# MacSet-L-V2_0_0_3.net
KiCad netlist of a schematic drawn in Altium Designer
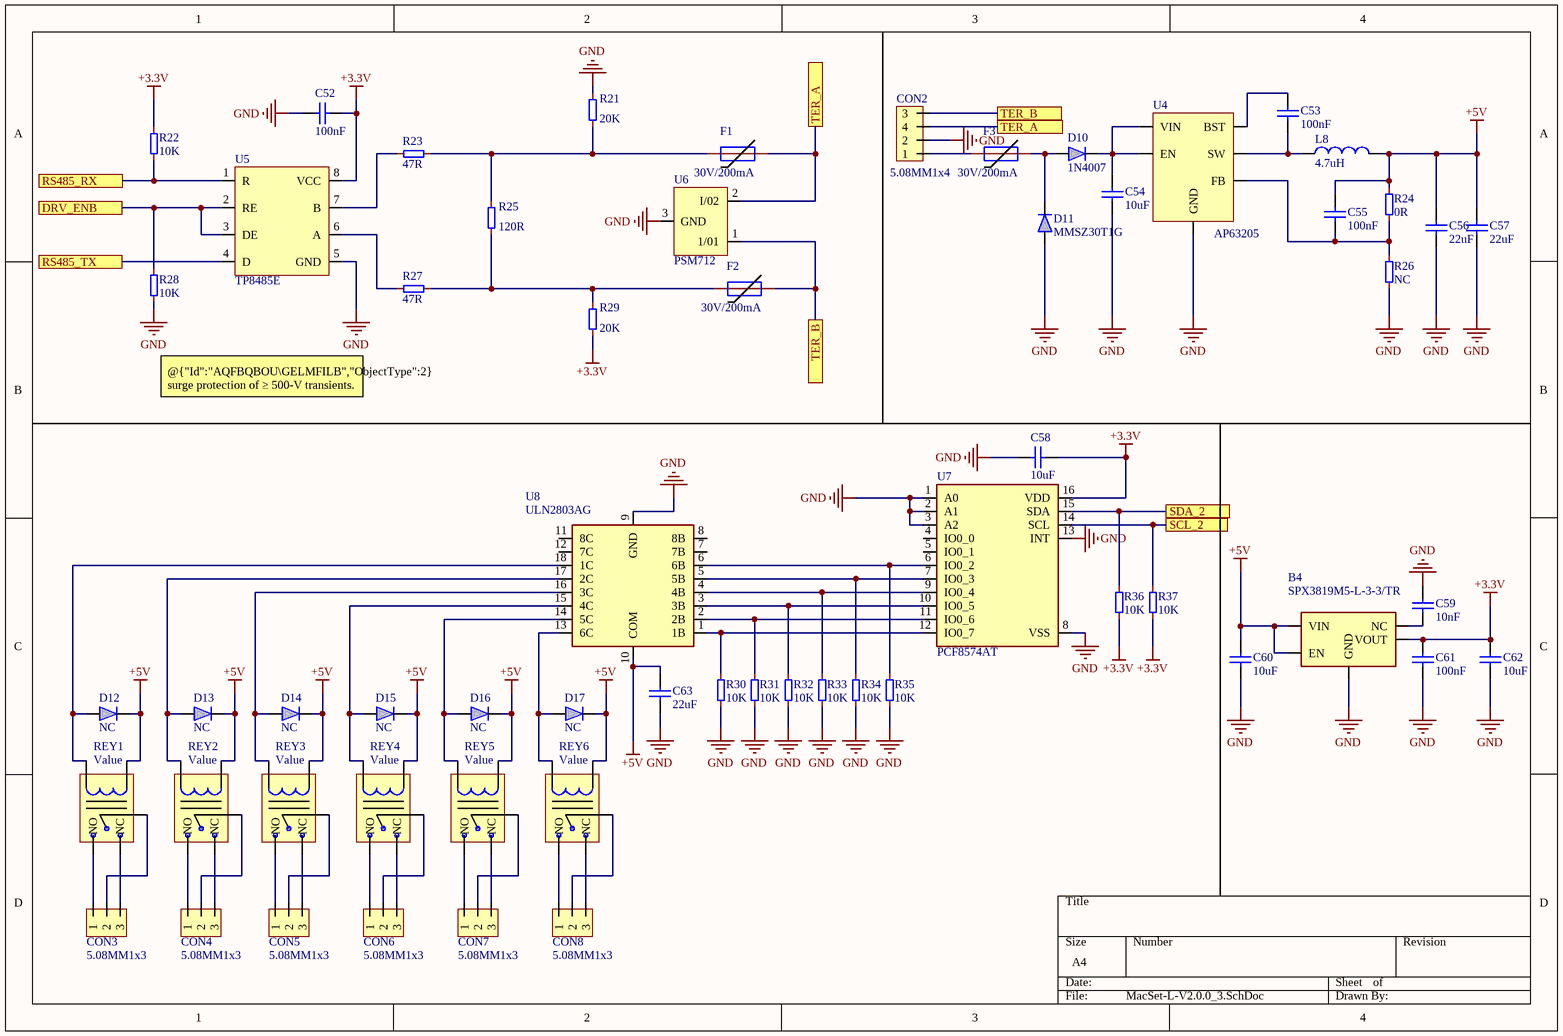
[diagram p0: MacSet-L-V2.0.0_3.SchDoc]

(export (version "E")
  (design (tool "Eeschema 10.0.6"))
  (components
    (comp (ref "B4")
      (value "SPX3819M5-L-3-3/TR")
      (footprint "SOT95P285X140-5N")
      (description "Linear Voltage Regulator IC Positive Fixed 1 3.3V Output 500mA SOT-25")
      (fields (field (name "MANUFACTURER") "MAX Linear"))
      (libsource (lib "macnman_2.0") (part "SPX3819M5"))
    )
    (comp (ref "C52")
      (value "100nF")
      (footprint "CAP0402")
      (description "Ceramic Capacitor X7R 0402 100nF 16V")
      (fields
        (field (name "MANUFACTURER_PART_NUMBER") "GRM155R71C104JA88D")
        (field (name "MANUFACTURER") "MURATA")
      )
      (libsource (lib "macnman_2.0") (part "Capa_0402"))
    )
    (comp (ref "C53")
      (value "100nF")
      (footprint "CAP0402")
      (description "Ceramic Capacitor C0G, NP0 0402 100nF 35V")
      (fields
        (field (name "MANUFACTURER_PART_NUMBER") "GRM155R61A104KA01J")
        (field (name "MANUFACTURER") "MURATA")
      )
      (libsource (lib "macnman_2.0") (part "Capa_0402"))
    )
    (comp (ref "C54")
      (value "10uF")
      (footprint "CAP0805")
      (description "MLCC - SMD/SMT 10 uF 50VDC 10% 0805 X6S")
      (fields
        (field (name "MANUFACTURER_PART_NUMBER") "CC0805KKX5R9BB106")
        (field (name "MANUFACTURER") "YAGEO")
      )
      (libsource (lib "macnman_2.0") (part "Capa_0805"))
    )
    (comp (ref "C55")
      (value "100nF")
      (footprint "CAP0402")
      (description "Ceramic Capacitor C0G, NP0 0402 100nF 35V")
      (fields
        (field (name "MANUFACTURER_PART_NUMBER") "GRM155R61A104KA01J")
        (field (name "MANUFACTURER") "MURATA")
      )
      (libsource (lib "macnman_2.0") (part "Capa_0402"))
    )
    (comp (ref "C56")
      (value "22uF")
      (footprint "CAP0805")
      (description "MLCC - SMD/SMT 22uF 10VDC 20% 0805 X6S")
      (fields
        (field (name "MANUFACTURER_PART_NUMBER") "CC0805KKX7R6BB226")
        (field (name "MANUFACTURER") "YAGEO")
      )
      (libsource (lib "macnman_2.0") (part "Capa_0805"))
    )
    (comp (ref "C57")
      (value "22uF")
      (footprint "CAP0805")
      (description "MLCC - SMD/SMT 22uF 10VDC 20% 0805 X6S")
      (fields
        (field (name "MANUFACTURER_PART_NUMBER") "CC0805KKX7R6BB226")
        (field (name "MANUFACTURER") "MURATA")
      )
      (libsource (lib "macnman_2.0") (part "Capa_0805"))
    )
    (comp (ref "C58")
      (value "10uF")
      (footprint "CAP0603")
      (description "Ceramic Capacitor X5R 0603 10uF 10V")
      (fields
        (field (name "MANUFACTURER_PART_NUMBER") "CL10A106KP8NNNL")
        (field (name "MANUFACTURER") "SAMSUNG")
      )
      (libsource (lib "macnman_2.0") (part "CAP_0603"))
    )
    (comp (ref "C59")
      (value "10nF")
      (footprint "CAP0402")
      (description "Ceramic Capacitor X7R 0402 10nF 50V")
      (fields
        (field (name "MANUFACTURER_PART_NUMBER") "GCM155R71H103KA55J")
        (field (name "MANUFACTURER") "Murata")
      )
      (libsource (lib "macnman_2.0") (part "CAP_0402"))
    )
    (comp (ref "C60")
      (value "10uF")
      (footprint "CAP0603")
      (description "Ceramic Capacitor X5R 0603 10uF 25V")
      (fields
        (field (name "MANUFACTURER_PART_NUMBER") "CL10A106MA8NRNC")
        (field (name "MANUFACTURER") "SAMSUNG")
      )
      (libsource (lib "macnman_2.0") (part "CAP_0603"))
    )
    (comp (ref "C61")
      (value "100nF")
      (footprint "CAP0402")
      (description "Ceramic Capacitor X7R 0402 100nF 50V")
      (fields
        (field (name "MANUFACTURER_PART_NUMBER") "CL05B104KA5NNNC")
        (field (name "MANUFACTURER") "SAMSUNG")
      )
      (libsource (lib "macnman_2.0") (part "CAP_0402"))
    )
    (comp (ref "C62")
      (value "10uF")
      (footprint "CAP0603")
      (description "Ceramic Capacitor X5R 0603 10uF 25V")
      (fields
        (field (name "MANUFACTURER_PART_NUMBER") "CL10A106MA8NRNC")
        (field (name "MANUFACTURER") "SAMSUNG")
      )
      (libsource (lib "macnman_2.0") (part "CAP_0603"))
    )
    (comp (ref "C63")
      (value "22uF")
      (footprint "CAP0805")
      (description "MLCC - SMD/SMT 22uF 10VDC 20% 0805 X6S")
      (fields
        (field (name "MANUFACTURER_PART_NUMBER") "CC0805KKX7R6BB226")
        (field (name "MANUFACTURER") "MURATA")
      )
      (libsource (lib "macnman_2.0") (part "Capa_0805"))
    )
    (comp (ref "CON2")
      (value "5.08MM1x4")
      (footprint "Screw Terminal Block 5.08x4")
      (description "5.08mm 1*4 Screw Terminal Block")
      (fields (field (name "MANUFACTURER") "XINYA"))
      (libsource (lib "macnman_2.0") (part "Screw Terminal Block 4x1 5.08mm"))
    )
    (comp (ref "CON3")
      (value "5.08MM1x3")
      (footprint "Screw Terminal Block 5.08x3")
      (description "5.08mm 1*3 Screw Terminal Block")
      (fields (field (name "MANUFACTURER_PART_NUMBER") "XY302V-3.5-3P") (field (name "MANUFACTURER") "XINYA"))
      (libsource (lib "macnman_2.0") (part "Screw Terminal Block 3x1 5.08mm"))
    )
    (comp (ref "CON4")
      (value "5.08MM1x3")
      (footprint "Screw Terminal Block 5.08x3")
      (description "5.08mm 1*3 Screw Terminal Block")
      (fields (field (name "MANUFACTURER_PART_NUMBER") "XY302V-3.5-3P") (field (name "MANUFACTURER") "XINYA"))
      (libsource (lib "macnman_2.0") (part "Screw Terminal Block 3x1 5.08mm"))
    )
    (comp (ref "CON5")
      (value "5.08MM1x3")
      (footprint "Screw Terminal Block 5.08x3")
      (description "5.08mm 1*3 Screw Terminal Block")
      (fields (field (name "MANUFACTURER_PART_NUMBER") "XY302V-3.5-3P") (field (name "MANUFACTURER") "XINYA"))
      (libsource (lib "macnman_2.0") (part "Screw Terminal Block 3x1 5.08mm"))
    )
    (comp (ref "CON6")
      (value "5.08MM1x3")
      (footprint "Screw Terminal Block 5.08x3")
      (description "5.08mm 1*3 Screw Terminal Block")
      (fields (field (name "MANUFACTURER_PART_NUMBER") "XY302V-3.5-3P") (field (name "MANUFACTURER") "XINYA"))
      (libsource (lib "macnman_2.0") (part "Screw Terminal Block 3x1 5.08mm"))
    )
    (comp (ref "CON7")
      (value "5.08MM1x3")
      (footprint "Screw Terminal Block 5.08x3")
      (description "5.08mm 1*3 Screw Terminal Block")
      (fields (field (name "MANUFACTURER_PART_NUMBER") "XY302V-3.5-3P") (field (name "MANUFACTURER") "XINYA"))
      (libsource (lib "macnman_2.0") (part "Screw Terminal Block 3x1 5.08mm"))
    )
    (comp (ref "CON8")
      (value "5.08MM1x3")
      (footprint "Screw Terminal Block 5.08x3")
      (description "5.08mm 1*3 Screw Terminal Block")
      (fields (field (name "MANUFACTURER_PART_NUMBER") "XY302V-3.5-3P") (field (name "MANUFACTURER") "XINYA"))
      (libsource (lib "macnman_2.0") (part "Screw Terminal Block 3x1 5.08mm"))
    )
    (comp (ref "D10")
      (value "1N4007")
      (footprint "Diode SMD 214AC")
      (description "Diode 1N4007 AO214AC")
      (fields (field (name "MANUFACTURER") "GENERIC"))
      (libsource (lib "macnman_2.0") (part "DIODE"))
    )
    (comp (ref "D11")
      (value "MMSZ30T1G")
      (footprint "SOD123-2")
      (description "MMSZ30T1G 30V 500mW Schottky Diodes & Rectifiers")
      (fields (field (name "MANUFACTURER") "Onsemi"))
      (libsource (lib "macnman_2.0") (part "BAT54T1G"))
    )
    (comp (ref "D12")
      (value "NC")
      (footprint "Diode SMD 214AC")
      (description "Diode 1N4007 AO214AC")
      (fields (field (name "MANUFACTURER_PART_NUMBER") "1N4007") (field (name "MANUFACTURER") "GENERIC"))
      (libsource (lib "macnman_2.0") (part "DIODE"))
    )
    (comp (ref "D13")
      (value "NC")
      (footprint "Diode SMD 214AC")
      (description "Diode 1N4007 AO214AC")
      (fields (field (name "MANUFACTURER_PART_NUMBER") "1N4007") (field (name "MANUFACTURER") "GENERIC"))
      (libsource (lib "macnman_2.0") (part "DIODE"))
    )
    (comp (ref "D14")
      (value "NC")
      (footprint "Diode SMD 214AC")
      (description "Diode 1N4007 AO214AC")
      (fields (field (name "MANUFACTURER_PART_NUMBER") "1N4007") (field (name "MANUFACTURER") "GENERIC"))
      (libsource (lib "macnman_2.0") (part "DIODE"))
    )
    (comp (ref "D15")
      (value "NC")
      (footprint "Diode SMD 214AC")
      (description "Diode 1N4007 AO214AC")
      (fields (field (name "MANUFACTURER_PART_NUMBER") "1N4007") (field (name "MANUFACTURER") "GENERIC"))
      (libsource (lib "macnman_2.0") (part "DIODE"))
    )
    (comp (ref "D16")
      (value "NC")
      (footprint "Diode SMD 214AC")
      (description "Diode 1N4007 AO214AC")
      (fields (field (name "MANUFACTURER_PART_NUMBER") "1N4007") (field (name "MANUFACTURER") "GENERIC"))
      (libsource (lib "macnman_2.0") (part "DIODE"))
    )
    (comp (ref "D17")
      (value "NC")
      (footprint "Diode SMD 214AC")
      (description "Diode 1N4007 AO214AC")
      (fields (field (name "MANUFACTURER_PART_NUMBER") "1N4007") (field (name "MANUFACTURER") "GENERIC"))
      (libsource (lib "macnman_2.0") (part "DIODE"))
    )
    (comp (ref "F1")
      (value "30V/200mA")
      (footprint "FUSE_1206")
      (description "Polymeric PTC Resettable Fuse 30V 200mA Surface Mount 1206")
      (fields
        (field (name "MANUFACTURER_PART_NUMBER") "nSMD020-30V")
        (field (name "MANUFACTURER") "TECHFUSE")
      )
      (libsource (lib "macnman_2.0") (part "FUSE_1206"))
    )
    (comp (ref "F2")
      (value "30V/200mA")
      (footprint "FUSE_1206")
      (description "Polymeric PTC Resettable Fuse 30V 200mA Surface Mount 1206")
      (fields
        (field (name "MANUFACTURER_PART_NUMBER") "nSMD020-30V")
        (field (name "MANUFACTURER") "TECHFUSE")
      )
      (libsource (lib "macnman_2.0") (part "FUSE_1206"))
    )
    (comp (ref "F3")
      (value "30V/200mA")
      (footprint "FUSE_1206")
      (description "Polymeric PTC Resettable Fuse 30V 200mA Surface Mount 1206")
      (fields
        (field (name "MANUFACTURER_PART_NUMBER") "nSMD020-30V")
        (field (name "MANUFACTURER") "TECHFUSE")
      )
      (libsource (lib "macnman_2.0") (part "FUSE_1206"))
    )
    (comp (ref "L8")
      (value "4.7uH")
      (footprint "IND_3x3x1.5MM")
      (description "1.09A 4.7uH ±3% 163mΩ 3015 Inductors")
      (fields
        (field (name "MANUFACTURER_PART_NUMBER") "SWPA3015S4R7MT")
        (field (name "MANUFACTURER") "SUNLORD")
      )
      (libsource (lib "macnman_2.0") (part "INDUCTOR"))
    )
    (comp (ref "R21")
      (value "20K")
      (footprint "RESC0402")
      (description "Resistor SMD 0402")
      (fields
        (field (name "MANUFACTURER_PART_NUMBER") "CRCW040220K0FKEDC")
        (field (name "MANUFACTURER") "YAGEO")
      )
      (libsource (lib "macnman_2.0") (part "RES_0402"))
    )
    (comp (ref "R22")
      (value "10K")
      (footprint "RESC0402")
      (description "Thick Film Resistors - SMD 1/16watt 10Kohms 0402 1% Commercial Use")
      (fields
        (field (name "MANUFACTURER_PART_NUMBER") "CRCW040210K0FKEDC")
        (field (name "MANUFACTURER") "Vishay")
      )
      (libsource (lib "macnman_2.0") (part "RES_0402"))
    )
    (comp (ref "R23")
      (value "47R")
      (footprint "RESC0603")
      (description "Thick Film Resistors - SMD 1/16Watt 47ohms 1% Commercial Use")
      (fields
        (field (name "MANUFACTURER_PART_NUMBER") "RC0402FR-0747RL")
        (field (name "MANUFACTURER") "Vishay")
      )
      (libsource (lib "macnman_2.0") (part "RES_0603"))
    )
    (comp (ref "R24")
      (value "0R")
      (footprint "RESC0402")
      (description "Thick Film Resistors - SMD 1/16watt 0R 1% 0402 Commercial Use")
      (fields
        (field (name "MANUFACTURER_PART_NUMBER") "RC0402FR-070RL")
        (field (name "MANUFACTURER") "Vishay")
      )
      (libsource (lib "macnman_2.0") (part "RES_0402"))
    )
    (comp (ref "R25")
      (value "120R")
      (footprint "RESC0402")
      (description "Resistor SMD 0402")
      (fields (field (name "Comment") "NC"))
      (libsource (lib "macnman_2.0") (part "RES_0402"))
    )
    (comp (ref "R26")
      (value "NC")
      (footprint "RESC0402")
      (description "Thick Film Resistors - SMD 1/16watt 10Kohms 0.1% 0402 Commercial Use")
      (fields
        (field (name "MANUFACTURER_PART_NUMBER") "MCS04020D1002BE000")
        (field (name "MANUFACTURER") "Vishay")
      )
      (libsource (lib "macnman_2.0") (part "RES_0402"))
    )
    (comp (ref "R27")
      (value "47R")
      (footprint "RESC0603")
      (description "Thick Film Resistors - SMD 1/16Watt 47ohms 1% Commercial Use")
      (fields
        (field (name "MANUFACTURER_PART_NUMBER") "RC0402FR-0747RL")
        (field (name "MANUFACTURER") "Vishay")
      )
      (libsource (lib "macnman_2.0") (part "RES_0603"))
    )
    (comp (ref "R28")
      (value "10K")
      (footprint "RESC0402")
      (description "Thick Film Resistors - SMD 1/16watt 10Kohms 0402 1% Commercial Use")
      (fields
        (field (name "MANUFACTURER_PART_NUMBER") "CRCW040210K0FKEDC")
        (field (name "MANUFACTURER") "Vishay")
      )
      (libsource (lib "macnman_2.0") (part "RES_0402"))
    )
    (comp (ref "R29")
      (value "20K")
      (footprint "RESC0402")
      (description "Resistor SMD 0402")
      (fields
        (field (name "MANUFACTURER_PART_NUMBER") "CRCW040220K0FKEDC")
        (field (name "MANUFACTURER") "YAGEO")
      )
      (libsource (lib "macnman_2.0") (part "RES_0402"))
    )
    (comp (ref "R30")
      (value "10K")
      (footprint "RESC0402")
      (description "Thick Film Resistors - SMD 1/16watt 10Kohms 0402 1% Commercial Use")
      (fields
        (field (name "MANUFACTURER_PART_NUMBER") "CRCW040210K0FKEDC")
        (field (name "MANUFACTURER") "Vishay")
      )
      (libsource (lib "macnman_2.0") (part "RES_0402"))
    )
    (comp (ref "R31")
      (value "10K")
      (footprint "RESC0402")
      (description "Thick Film Resistors - SMD 1/16watt 10Kohms 0402 1% Commercial Use")
      (fields
        (field (name "MANUFACTURER_PART_NUMBER") "CRCW040210K0FKEDC")
        (field (name "MANUFACTURER") "Vishay")
      )
      (libsource (lib "macnman_2.0") (part "RES_0402"))
    )
    (comp (ref "R32")
      (value "10K")
      (footprint "RESC0402")
      (description "Thick Film Resistors - SMD 1/16watt 10Kohms 0402 1% Commercial Use")
      (fields
        (field (name "MANUFACTURER_PART_NUMBER") "CRCW040210K0FKEDC")
        (field (name "MANUFACTURER") "Vishay")
      )
      (libsource (lib "macnman_2.0") (part "RES_0402"))
    )
    (comp (ref "R33")
      (value "10K")
      (footprint "RESC0402")
      (description "Thick Film Resistors - SMD 1/16watt 10Kohms 0402 1% Commercial Use")
      (fields
        (field (name "MANUFACTURER_PART_NUMBER") "CRCW040210K0FKEDC")
        (field (name "MANUFACTURER") "Vishay")
      )
      (libsource (lib "macnman_2.0") (part "RES_0402"))
    )
    (comp (ref "R34")
      (value "10K")
      (footprint "RESC0402")
      (description "Thick Film Resistors - SMD 1/16watt 10Kohms 0402 1% Commercial Use")
      (fields
        (field (name "MANUFACTURER_PART_NUMBER") "CRCW040210K0FKEDC")
        (field (name "MANUFACTURER") "Vishay")
      )
      (libsource (lib "macnman_2.0") (part "RES_0402"))
    )
    (comp (ref "R35")
      (value "10K")
      (footprint "RESC0402")
      (description "Thick Film Resistors - SMD 1/16watt 10Kohms 0402 1% Commercial Use")
      (fields
        (field (name "MANUFACTURER_PART_NUMBER") "CRCW040210K0FKEDC")
        (field (name "MANUFACTURER") "Vishay")
      )
      (libsource (lib "macnman_2.0") (part "RES_0402"))
    )
    (comp (ref "R36")
      (value "10K")
      (footprint "RESC0402")
      (description "Thick Film Resistors - SMD 1/16watt 10Kohms 0402 1% Commercial Use")
      (fields
        (field (name "MANUFACTURER_PART_NUMBER") "CRCW040210K0FKEDC")
        (field (name "MANUFACTURER") "Vishay")
      )
      (libsource (lib "macnman_2.0") (part "RES_0402"))
    )
    (comp (ref "R37")
      (value "10K")
      (footprint "RESC0402")
      (description "Thick Film Resistors - SMD 1/16watt 10Kohms 0402 1% Commercial Use")
      (fields
        (field (name "MANUFACTURER_PART_NUMBER") "CRCW040210K0FKEDC")
        (field (name "MANUFACTURER") "Vishay")
      )
      (libsource (lib "macnman_2.0") (part "RES_0402"))
    )
    (comp (ref "REY1")
      (value "Value")
      (footprint "Relay")
      (description "5V Sugar Cube Relay 44mA")
      (libsource (lib "macnman_2.0") (part "Relay"))
    )
    (comp (ref "REY2")
      (value "Value")
      (footprint "Relay")
      (description "5V Sugar Cube Relay 44mA")
      (libsource (lib "macnman_2.0") (part "Relay"))
    )
    (comp (ref "REY3")
      (value "Value")
      (footprint "Relay")
      (description "5V Sugar Cube Relay 44mA")
      (libsource (lib "macnman_2.0") (part "Relay"))
    )
    (comp (ref "REY4")
      (value "Value")
      (footprint "Relay")
      (description "5V Sugar Cube Relay 44mA")
      (libsource (lib "macnman_2.0") (part "Relay"))
    )
    (comp (ref "REY5")
      (value "Value")
      (footprint "Relay")
      (description "5V Sugar Cube Relay 44mA")
      (libsource (lib "macnman_2.0") (part "Relay"))
    )
    (comp (ref "REY6")
      (value "Value")
      (footprint "Relay")
      (description "5V Sugar Cube Relay 44mA")
      (libsource (lib "macnman_2.0") (part "Relay"))
    )
    (comp (ref "U4")
      (value "AP63205")
      (footprint "SOT23-6")
      (description "AP63205 - Switching Voltage Regulators 5V OUT DCDC 3.8V-32V Conv HV Buck TSOT26 T&R 3K")
      (fields
        (field (name "MANUFACTURER_PART_NUMBER") "AP63205QWU-7")
        (field (name "MANUFACTURER") "Diodes Incorporated")
      )
      (libsource (lib "macnman_2.0") (part "AP63205"))
    )
    (comp (ref "U5")
      (value "TP8485E")
      (footprint "SOIC8")
      (description "TP8485E RS485 Tranreciver 3V-5.5V SOIC8")
      (fields (field (name "MANUFACTURER") "3PEAK") (field (name "MANUFACTURER_PART_NUMBER") "TP8485"))
      (libsource (lib "macnman_2.0") (part "TP8485E"))
    )
    (comp (ref "U6")
      (value "PSM712")
      (footprint "SOT23")
      (description "Asymmerical TVS Diode for Extended Common-Mode RS-485")
      (fields
        (field (name "MANUFACTURER_PART_NUMBER") "SM712H-TP-B002")
        (field (name "MANUFACTURER") "Micro Commercial Components (MCC)")
      )
      (libsource (lib "macnman_2.0") (part "PSM712"))
    )
    (comp (ref "U7")
      (value "PCF8574AT")
      (footprint "SOIC-16-W")
      (description "PCF8574AT 8Bit I2C GPIO Expander 16 Pin")
      (fields (field (name "MANUFACTURER") "NXP Semiconductors"))
      (libsource (lib "macnman_2.0") (part "PCF8574AT"))
    )
    (comp (ref "U8")
      (value "ULN2803AG")
      (footprint "SOIC-18-W")
      (description "ULN2803C device is a 50V, 500mA Darlington\r\ntransistor array")
      (fields (field (name "MANUFACTURER_PART_NUMBER") "ULN2803A") (field (name "MANUFACTURER") "UMW"))
      (libsource (lib "macnman_2.0") (part "ULN2803AG"))
    )
  )
  (nets
    (net (code "1") (name "+3.3V") (class "Default")
      (node (ref "B4") (pin "5") (pinfunction "VOUT_5") (pintype "passive"))
      (node (ref "C52") (pin "2") (pinfunction "2_2") (pintype "passive"))
      (node (ref "C58") (pin "2") (pinfunction "2_2") (pintype "passive"))
      (node (ref "C61") (pin "2") (pinfunction "2_2") (pintype "passive"))
      (node (ref "C62") (pin "2") (pinfunction "2_2") (pintype "passive"))
      (node (ref "R22") (pin "2") (pinfunction "2_2") (pintype "passive"))
      (node (ref "R29") (pin "1") (pinfunction "1_1") (pintype "passive"))
      (node (ref "R36") (pin "1") (pinfunction "1_1") (pintype "passive"))
      (node (ref "R37") (pin "1") (pinfunction "1_1") (pintype "passive"))
      (node (ref "U5") (pin "8") (pinfunction "VCC_8") (pintype "passive"))
      (node (ref "U7") (pin "16") (pinfunction "VDD_16") (pintype "passive"))
    )
    (net (code "2") (name "+5V") (class "Default")
      (node (ref "B4") (pin "1") (pinfunction "VIN_1") (pintype "passive"))
      (node (ref "B4") (pin "3") (pinfunction "EN_3") (pintype "passive"))
      (node (ref "C55") (pin "2") (pinfunction "2_2") (pintype "passive"))
      (node (ref "C56") (pin "2") (pinfunction "2_2") (pintype "passive"))
      (node (ref "C57") (pin "2") (pinfunction "2_2") (pintype "passive"))
      (node (ref "C60") (pin "2") (pinfunction "2_2") (pintype "passive"))
      (node (ref "C63") (pin "1") (pinfunction "1_1") (pintype "passive"))
      (node (ref "D12") (pin "1") (pinfunction "K_1") (pintype "passive"))
      (node (ref "D13") (pin "1") (pinfunction "K_1") (pintype "passive"))
      (node (ref "D14") (pin "1") (pinfunction "K_1") (pintype "passive"))
      (node (ref "D15") (pin "1") (pinfunction "K_1") (pintype "passive"))
      (node (ref "D16") (pin "1") (pinfunction "K_1") (pintype "passive"))
      (node (ref "D17") (pin "1") (pinfunction "K_1") (pintype "passive"))
      (node (ref "L8") (pin "2") (pintype "passive"))
      (node (ref "R24") (pin "1") (pinfunction "1_1") (pintype "passive"))
      (node (ref "REY1") (pin "1") (pinfunction "+_1") (pintype "passive"))
      (node (ref "REY2") (pin "1") (pinfunction "+_1") (pintype "passive"))
      (node (ref "REY3") (pin "1") (pinfunction "+_1") (pintype "passive"))
      (node (ref "REY4") (pin "1") (pinfunction "+_1") (pintype "passive"))
      (node (ref "REY5") (pin "1") (pinfunction "+_1") (pintype "passive"))
      (node (ref "REY6") (pin "1") (pinfunction "+_1") (pintype "passive"))
      (node (ref "U8") (pin "10") (pinfunction "COM_10") (pintype "passive"))
    )
    (net (code "3") (name "/DRV_ENB") (class "Default")
      (node (ref "R28") (pin "2") (pinfunction "2_2") (pintype "passive"))
      (node (ref "U5") (pin "2") (pinfunction "RE_2") (pintype "passive"))
      (node (ref "U5") (pin "3") (pinfunction "DE_3") (pintype "passive"))
    )
    (net (code "4") (name "/RS485_RX") (class "Default")
      (node (ref "R22") (pin "1") (pinfunction "1_1") (pintype "passive"))
      (node (ref "U5") (pin "1") (pinfunction "R_1") (pintype "passive"))
    )
    (net (code "5") (name "/RS485_TX") (class "Default")
      (node (ref "U5") (pin "4") (pinfunction "D_4") (pintype "passive"))
    )
    (net (code "6") (name "/SCL_2") (class "Default")
      (node (ref "R37") (pin "2") (pinfunction "2_2") (pintype "passive"))
      (node (ref "U7") (pin "14") (pinfunction "SCL_14") (pintype "passive"))
    )
    (net (code "7") (name "/SDA_2") (class "Default")
      (node (ref "R36") (pin "2") (pinfunction "2_2") (pintype "passive"))
      (node (ref "U7") (pin "15") (pinfunction "SDA_15") (pintype "passive"))
    )
    (net (code "8") (name "/TER_A") (class "Default")
      (node (ref "CON2") (pin "4") (pinfunction "4_4") (pintype "passive"))
      (node (ref "F1") (pin "2") (pinfunction "50_2") (pintype "passive"))
      (node (ref "U6") (pin "2") (pinfunction "I/02_2") (pintype "passive"))
    )
    (net (code "9") (name "/TER_B") (class "Default")
      (node (ref "CON2") (pin "3") (pinfunction "3_3") (pintype "passive"))
      (node (ref "F2") (pin "2") (pinfunction "50_2") (pintype "passive"))
      (node (ref "U6") (pin "1") (pinfunction "1/01_1") (pintype "passive"))
    )
    (net (code "10") (name "GND") (class "Default")
      (node (ref "B4") (pin "2") (pinfunction "GND_2") (pintype "passive"))
      (node (ref "C52") (pin "1") (pinfunction "1_1") (pintype "passive"))
      (node (ref "C54") (pin "1") (pinfunction "1_1") (pintype "passive"))
      (node (ref "C56") (pin "1") (pinfunction "1_1") (pintype "passive"))
      (node (ref "C57") (pin "1") (pinfunction "1_1") (pintype "passive"))
      (node (ref "C58") (pin "1") (pinfunction "1_1") (pintype "passive"))
      (node (ref "C59") (pin "1") (pinfunction "1_1") (pintype "passive"))
      (node (ref "C60") (pin "1") (pinfunction "1_1") (pintype "passive"))
      (node (ref "C61") (pin "1") (pinfunction "1_1") (pintype "passive"))
      (node (ref "C62") (pin "1") (pinfunction "1_1") (pintype "passive"))
      (node (ref "C63") (pin "2") (pinfunction "2_2") (pintype "passive"))
      (node (ref "CON2") (pin "2") (pinfunction "2_2") (pintype "passive"))
      (node (ref "D11") (pin "2") (pinfunction "A_2") (pintype "passive"))
      (node (ref "R21") (pin "2") (pinfunction "2_2") (pintype "passive"))
      (node (ref "R26") (pin "2") (pinfunction "2_2") (pintype "passive"))
      (node (ref "R28") (pin "1") (pinfunction "1_1") (pintype "passive"))
      (node (ref "R30") (pin "1") (pinfunction "1_1") (pintype "passive"))
      (node (ref "R31") (pin "1") (pinfunction "1_1") (pintype "passive"))
      (node (ref "R32") (pin "1") (pinfunction "1_1") (pintype "passive"))
      (node (ref "R33") (pin "1") (pinfunction "1_1") (pintype "passive"))
      (node (ref "R34") (pin "1") (pinfunction "1_1") (pintype "passive"))
      (node (ref "R35") (pin "1") (pinfunction "1_1") (pintype "passive"))
      (node (ref "U4") (pin "4") (pinfunction "GND_4") (pintype "passive"))
      (node (ref "U5") (pin "5") (pinfunction "GND_5") (pintype "passive"))
      (node (ref "U6") (pin "3") (pinfunction "GND_3") (pintype "passive"))
      (node (ref "U7") (pin "1") (pinfunction "A0_1") (pintype "power_in"))
      (node (ref "U7") (pin "13") (pinfunction "INT_13") (pintype "passive"))
      (node (ref "U7") (pin "2") (pinfunction "A1_2") (pintype "power_in"))
      (node (ref "U7") (pin "3") (pinfunction "A2_3") (pintype "passive"))
      (node (ref "U7") (pin "8") (pinfunction "VSS_8") (pintype "passive"))
      (node (ref "U8") (pin "9") (pinfunction "GND_9") (pintype "passive"))
    )
    (net (code "11") (name "Net-(B4-NC)") (class "Default")
      (node (ref "B4") (pin "4") (pinfunction "NC_4") (pintype "passive"))
      (node (ref "C59") (pin "2") (pinfunction "2_2") (pintype "passive"))
    )
    (net (code "12") (name "Net-(D10-A)") (class "Default")
      (node (ref "D10") (pin "2") (pinfunction "A_2") (pintype "passive"))
      (node (ref "D11") (pin "1") (pinfunction "K_1") (pintype "passive"))
      (node (ref "F3") (pin "2") (pinfunction "50_2") (pintype "passive"))
    )
    (net (code "13") (name "Net-(D10-K)") (class "Default")
      (node (ref "C54") (pin "2") (pinfunction "2_2") (pintype "passive"))
      (node (ref "D10") (pin "1") (pinfunction "K_1") (pintype "passive"))
      (node (ref "U4") (pin "2") (pinfunction "EN_2") (pintype "passive"))
      (node (ref "U4") (pin "3") (pinfunction "VIN_3") (pintype "passive"))
    )
    (net (code "14") (name "Net-(D12-A)") (class "Default")
      (node (ref "D12") (pin "2") (pinfunction "A_2") (pintype "passive"))
      (node (ref "REY1") (pin "3") (pinfunction "-_3") (pintype "passive"))
      (node (ref "U8") (pin "18") (pinfunction "1C_18") (pintype "passive"))
    )
    (net (code "15") (name "Net-(D13-A)") (class "Default")
      (node (ref "D13") (pin "2") (pinfunction "A_2") (pintype "passive"))
      (node (ref "REY2") (pin "3") (pinfunction "-_3") (pintype "passive"))
      (node (ref "U8") (pin "17") (pinfunction "2C_17") (pintype "passive"))
    )
    (net (code "16") (name "Net-(D14-A)") (class "Default")
      (node (ref "D14") (pin "2") (pinfunction "A_2") (pintype "passive"))
      (node (ref "REY3") (pin "3") (pinfunction "-_3") (pintype "passive"))
      (node (ref "U8") (pin "16") (pinfunction "3C_16") (pintype "passive"))
    )
    (net (code "17") (name "Net-(D15-A)") (class "Default")
      (node (ref "D15") (pin "2") (pinfunction "A_2") (pintype "passive"))
      (node (ref "REY4") (pin "3") (pinfunction "-_3") (pintype "passive"))
      (node (ref "U8") (pin "15") (pinfunction "4C_15") (pintype "passive"))
    )
    (net (code "18") (name "Net-(D16-A)") (class "Default")
      (node (ref "D16") (pin "2") (pinfunction "A_2") (pintype "passive"))
      (node (ref "REY5") (pin "3") (pinfunction "-_3") (pintype "passive"))
      (node (ref "U8") (pin "14") (pinfunction "5C_14") (pintype "passive"))
    )
    (net (code "19") (name "Net-(D17-A)") (class "Default")
      (node (ref "D17") (pin "2") (pinfunction "A_2") (pintype "passive"))
      (node (ref "REY6") (pin "3") (pinfunction "-_3") (pintype "passive"))
      (node (ref "U8") (pin "13") (pinfunction "6C_13") (pintype "passive"))
    )
    (net (code "20") (name "Net-(F1-49)") (class "Default")
      (node (ref "F1") (pin "1") (pinfunction "49_1") (pintype "passive"))
      (node (ref "R21") (pin "1") (pinfunction "1_1") (pintype "passive"))
      (node (ref "R23") (pin "2") (pinfunction "2_2") (pintype "passive"))
      (node (ref "R25") (pin "2") (pinfunction "2_2") (pintype "passive"))
    )
    (net (code "21") (name "Net-(F2-49)") (class "Default")
      (node (ref "F2") (pin "1") (pinfunction "49_1") (pintype "passive"))
      (node (ref "R25") (pin "1") (pinfunction "1_1") (pintype "passive"))
      (node (ref "R27") (pin "2") (pinfunction "2_2") (pintype "passive"))
      (node (ref "R29") (pin "2") (pinfunction "2_2") (pintype "passive"))
    )
    (net (code "22") (name "Net-(F3-49)") (class "Default")
      (node (ref "CON2") (pin "1") (pinfunction "1_1") (pintype "passive"))
      (node (ref "F3") (pin "1") (pinfunction "49_1") (pintype "passive"))
    )
    (net (code "23") (name "Net-(REY1-CM)") (class "Default")
      (node (ref "CON3") (pin "2") (pinfunction "2_2") (pintype "passive"))
      (node (ref "REY1") (pin "2") (pinfunction "CM_2") (pintype "passive"))
    )
    (net (code "24") (name "Net-(REY1-NC)") (class "Default")
      (node (ref "CON3") (pin "3") (pinfunction "3_3") (pintype "passive"))
      (node (ref "REY1") (pin "5") (pinfunction "NC_5") (pintype "passive"))
    )
    (net (code "25") (name "Net-(REY1-NO)") (class "Default")
      (node (ref "CON3") (pin "1") (pinfunction "1_1") (pintype "passive"))
      (node (ref "REY1") (pin "4") (pinfunction "NO_4") (pintype "passive"))
    )
    (net (code "26") (name "Net-(REY2-CM)") (class "Default")
      (node (ref "CON4") (pin "2") (pinfunction "2_2") (pintype "passive"))
      (node (ref "REY2") (pin "2") (pinfunction "CM_2") (pintype "passive"))
    )
    (net (code "27") (name "Net-(REY2-NC)") (class "Default")
      (node (ref "CON4") (pin "3") (pinfunction "3_3") (pintype "passive"))
      (node (ref "REY2") (pin "5") (pinfunction "NC_5") (pintype "passive"))
    )
    (net (code "28") (name "Net-(REY2-NO)") (class "Default")
      (node (ref "CON4") (pin "1") (pinfunction "1_1") (pintype "passive"))
      (node (ref "REY2") (pin "4") (pinfunction "NO_4") (pintype "passive"))
    )
    (net (code "29") (name "Net-(REY3-CM)") (class "Default")
      (node (ref "CON5") (pin "2") (pinfunction "2_2") (pintype "passive"))
      (node (ref "REY3") (pin "2") (pinfunction "CM_2") (pintype "passive"))
    )
    (net (code "30") (name "Net-(REY3-NC)") (class "Default")
      (node (ref "CON5") (pin "3") (pinfunction "3_3") (pintype "passive"))
      (node (ref "REY3") (pin "5") (pinfunction "NC_5") (pintype "passive"))
    )
    (net (code "31") (name "Net-(REY3-NO)") (class "Default")
      (node (ref "CON5") (pin "1") (pinfunction "1_1") (pintype "passive"))
      (node (ref "REY3") (pin "4") (pinfunction "NO_4") (pintype "passive"))
    )
    (net (code "32") (name "Net-(REY4-CM)") (class "Default")
      (node (ref "CON6") (pin "2") (pinfunction "2_2") (pintype "passive"))
      (node (ref "REY4") (pin "2") (pinfunction "CM_2") (pintype "passive"))
    )
    (net (code "33") (name "Net-(REY4-NC)") (class "Default")
      (node (ref "CON6") (pin "3") (pinfunction "3_3") (pintype "passive"))
      (node (ref "REY4") (pin "5") (pinfunction "NC_5") (pintype "passive"))
    )
    (net (code "34") (name "Net-(REY4-NO)") (class "Default")
      (node (ref "CON6") (pin "1") (pinfunction "1_1") (pintype "passive"))
      (node (ref "REY4") (pin "4") (pinfunction "NO_4") (pintype "passive"))
    )
    (net (code "35") (name "Net-(REY5-CM)") (class "Default")
      (node (ref "CON7") (pin "2") (pinfunction "2_2") (pintype "passive"))
      (node (ref "REY5") (pin "2") (pinfunction "CM_2") (pintype "passive"))
    )
    (net (code "36") (name "Net-(REY5-NC)") (class "Default")
      (node (ref "CON7") (pin "3") (pinfunction "3_3") (pintype "passive"))
      (node (ref "REY5") (pin "5") (pinfunction "NC_5") (pintype "passive"))
    )
    (net (code "37") (name "Net-(REY5-NO)") (class "Default")
      (node (ref "CON7") (pin "1") (pinfunction "1_1") (pintype "passive"))
      (node (ref "REY5") (pin "4") (pinfunction "NO_4") (pintype "passive"))
    )
    (net (code "38") (name "Net-(REY6-CM)") (class "Default")
      (node (ref "CON8") (pin "2") (pinfunction "2_2") (pintype "passive"))
      (node (ref "REY6") (pin "2") (pinfunction "CM_2") (pintype "passive"))
    )
    (net (code "39") (name "Net-(REY6-NC)") (class "Default")
      (node (ref "CON8") (pin "3") (pinfunction "3_3") (pintype "passive"))
      (node (ref "REY6") (pin "5") (pinfunction "NC_5") (pintype "passive"))
    )
    (net (code "40") (name "Net-(REY6-NO)") (class "Default")
      (node (ref "CON8") (pin "1") (pinfunction "1_1") (pintype "passive"))
      (node (ref "REY6") (pin "4") (pinfunction "NO_4") (pintype "passive"))
    )
    (net (code "41") (name "Net-(U4-BST)") (class "Default")
      (node (ref "C53") (pin "2") (pinfunction "2_2") (pintype "passive"))
      (node (ref "U4") (pin "6") (pinfunction "BST_6") (pintype "passive"))
    )
    (net (code "42") (name "Net-(U4-FB)") (class "Default")
      (node (ref "C55") (pin "1") (pinfunction "1_1") (pintype "passive"))
      (node (ref "R24") (pin "2") (pinfunction "2_2") (pintype "passive"))
      (node (ref "R26") (pin "1") (pinfunction "1_1") (pintype "passive"))
      (node (ref "U4") (pin "1") (pinfunction "FB_1") (pintype "passive"))
    )
    (net (code "43") (name "Net-(U4-SW)") (class "Default")
      (node (ref "C53") (pin "1") (pinfunction "1_1") (pintype "passive"))
      (node (ref "L8") (pin "1") (pintype "passive"))
      (node (ref "U4") (pin "5") (pinfunction "SW_5") (pintype "passive"))
    )
    (net (code "44") (name "Net-(U5-A)") (class "Default")
      (node (ref "R27") (pin "1") (pinfunction "1_1") (pintype "passive"))
      (node (ref "U5") (pin "6") (pinfunction "A_6") (pintype "passive"))
    )
    (net (code "45") (name "Net-(U5-B)") (class "Default")
      (node (ref "R23") (pin "1") (pinfunction "1_1") (pintype "passive"))
      (node (ref "U5") (pin "7") (pinfunction "B_7") (pintype "passive"))
    )
    (net (code "46") (name "Net-(U7-IO0_2)") (class "Default")
      (node (ref "R35") (pin "2") (pinfunction "2_2") (pintype "passive"))
      (node (ref "U7") (pin "6") (pinfunction "IO0_2_6") (pintype "passive"))
      (node (ref "U8") (pin "6") (pinfunction "6B_6") (pintype "passive"))
    )
    (net (code "47") (name "Net-(U7-IO0_3)") (class "Default")
      (node (ref "R34") (pin "2") (pinfunction "2_2") (pintype "passive"))
      (node (ref "U7") (pin "7") (pinfunction "IO0_3_7") (pintype "passive"))
      (node (ref "U8") (pin "5") (pinfunction "5B_5") (pintype "passive"))
    )
    (net (code "48") (name "Net-(U7-IO0_4)") (class "Default")
      (node (ref "R33") (pin "2") (pinfunction "2_2") (pintype "passive"))
      (node (ref "U7") (pin "9") (pinfunction "IO0_4_9") (pintype "passive"))
      (node (ref "U8") (pin "4") (pinfunction "4B_4") (pintype "passive"))
    )
    (net (code "49") (name "Net-(U7-IO0_5)") (class "Default")
      (node (ref "R32") (pin "2") (pinfunction "2_2") (pintype "passive"))
      (node (ref "U7") (pin "10") (pinfunction "IO0_5_10") (pintype "passive"))
      (node (ref "U8") (pin "3") (pinfunction "3B_3") (pintype "passive"))
    )
    (net (code "50") (name "Net-(U7-IO0_6)") (class "Default")
      (node (ref "R31") (pin "2") (pinfunction "2_2") (pintype "passive"))
      (node (ref "U7") (pin "11") (pinfunction "IO0_6_11") (pintype "passive"))
      (node (ref "U8") (pin "2") (pinfunction "2B_2") (pintype "power_in"))
    )
    (net (code "51") (name "Net-(U7-IO0_7)") (class "Default")
      (node (ref "R30") (pin "2") (pinfunction "2_2") (pintype "passive"))
      (node (ref "U7") (pin "12") (pinfunction "IO0_7_12") (pintype "passive"))
      (node (ref "U8") (pin "1") (pinfunction "1B_1") (pintype "power_in"))
    )
    (net (code "52") (name "unconnected-(U7-IO0_0-Pad4)") (class "Default")
      (node (ref "U7") (pin "4") (pinfunction "IO0_0_4") (pintype "passive"))
    )
    (net (code "53") (name "unconnected-(U7-IO0_1-Pad5)") (class "Default")
      (node (ref "U7") (pin "5") (pinfunction "IO0_1_5") (pintype "passive"))
    )
    (net (code "54") (name "unconnected-(U8-7B-Pad7)") (class "Default")
      (node (ref "U8") (pin "7") (pinfunction "7B_7") (pintype "passive"))
    )
    (net (code "55") (name "unconnected-(U8-7C-Pad12)") (class "Default")
      (node (ref "U8") (pin "12") (pinfunction "7C_12") (pintype "passive"))
    )
    (net (code "56") (name "unconnected-(U8-8B-Pad8)") (class "Default")
      (node (ref "U8") (pin "8") (pinfunction "8B_8") (pintype "passive"))
    )
    (net (code "57") (name "unconnected-(U8-8C-Pad11)") (class "Default")
      (node (ref "U8") (pin "11") (pinfunction "8C_11") (pintype "passive"))
    )
  )
)
